# B008_-_Xino_RF_v1_5.net
KiCad netlist of a schematic drawn in EAGLE
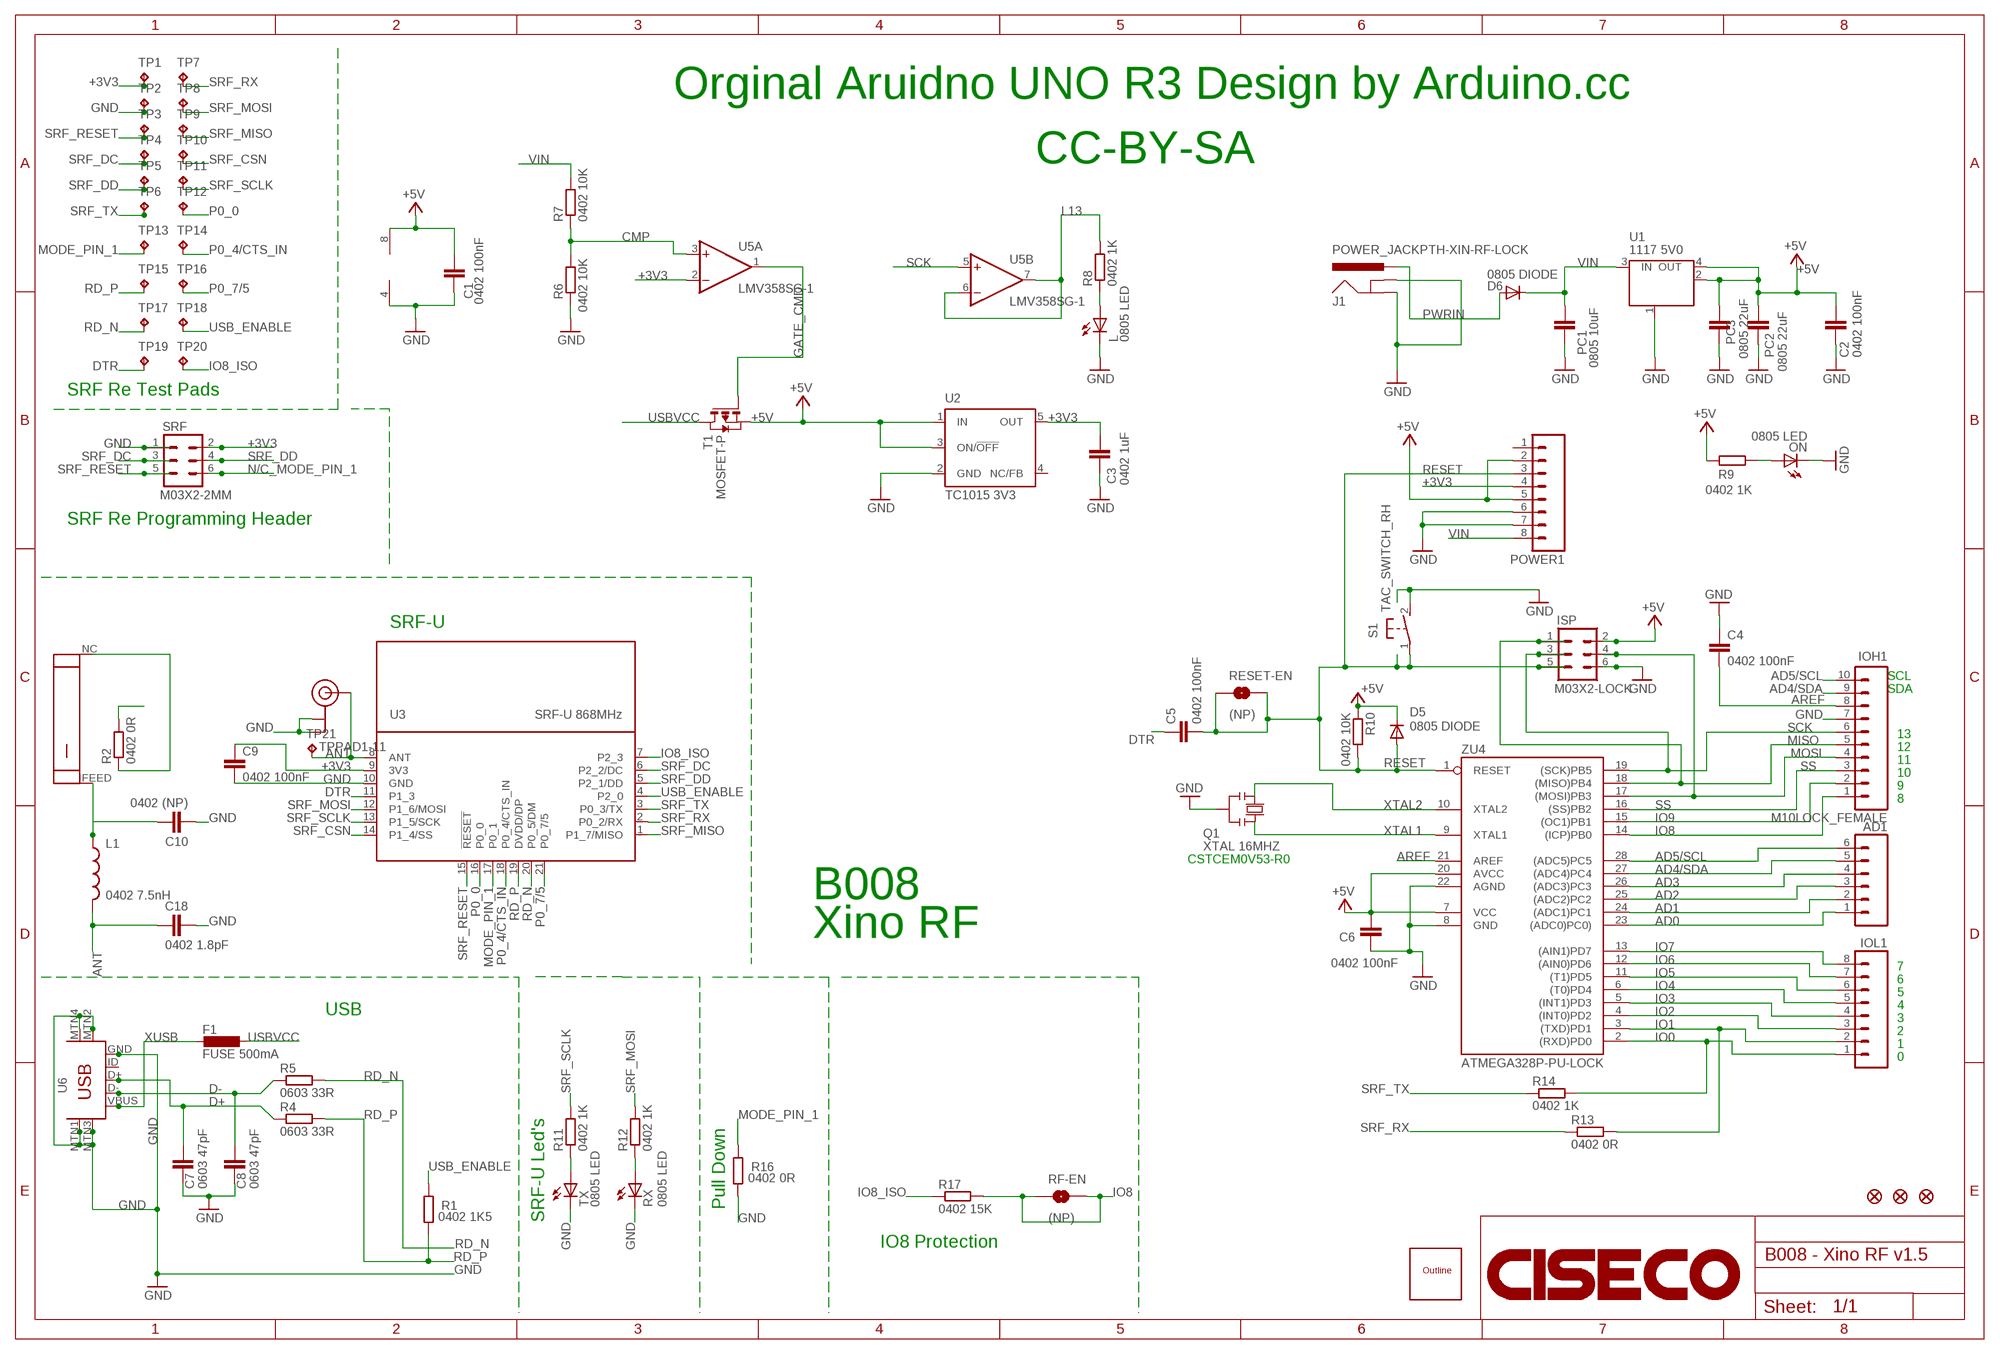
[diagram p0: schematic, sheet 1]

(export (version "E")
  (design (tool "Eeschema 10.0.6"))
  (components
    (comp (ref "AD1")
      (value "M06LOCK_FEMALE")
      (footprint "eagle-import:1X06_LOCK_FEMALE")
      (libsource (lib "eagle-import") (part "M06LOCK_FEMALE"))
    )
    (comp (ref "C1")
      (value "0402 100nF")
      (footprint "eagle-import:C0402-SMALLER")
      (libsource (lib "eagle-import") (part "C-EUC0402-SMALLER"))
    )
    (comp (ref "C2")
      (value "0402 100nF")
      (footprint "eagle-import:C0402-SMALLER")
      (libsource (lib "eagle-import") (part "C-EUC0402-SMALLER"))
    )
    (comp (ref "C3")
      (value "0402 1uF")
      (footprint "eagle-import:C0402-SMALLER")
      (libsource (lib "eagle-import") (part "C-EUC0402-SMALLER"))
    )
    (comp (ref "C4")
      (value "0402 100nF")
      (footprint "eagle-import:C0402-SMALLER")
      (libsource (lib "eagle-import") (part "C-EUC0402-SMALLER"))
    )
    (comp (ref "C5")
      (value "0402 100nF")
      (footprint "eagle-import:C0402-SMALLER")
      (libsource (lib "eagle-import") (part "C-EUC0402-SMALLER"))
    )
    (comp (ref "C6")
      (value "0402 100nF")
      (footprint "eagle-import:C0603-ROUND")
      (libsource (lib "eagle-import") (part "C-EU0603-RND"))
    )
    (comp (ref "C7")
      (value "0603 47pF")
      (footprint "eagle-import:C0603K-SMALL")
      (libsource (lib "eagle-import") (part "C-EUC0603K-SMALL"))
    )
    (comp (ref "C8")
      (value "0603 47pF")
      (footprint "eagle-import:C0603K-SMALL")
      (libsource (lib "eagle-import") (part "C-EUC0603K-SMALL"))
    )
    (comp (ref "C9")
      (value "0402 100nF")
      (footprint "eagle-import:C0402-SMALLER")
      (libsource (lib "eagle-import") (part "C-EUC0402-SMALLER"))
    )
    (comp (ref "C10")
      (value "0402 (NP)")
      (footprint "eagle-import:C0402-SMALLER")
      (libsource (lib "eagle-import") (part "C-EUC0402-SMALLER"))
    )
    (comp (ref "C18")
      (value "0402 1.8pF")
      (footprint "eagle-import:C0402-SMALLER")
      (libsource (lib "eagle-import") (part "C-EUC0402-SMALLER"))
    )
    (comp (ref "D5")
      (value "0805 DIODE")
      (footprint "eagle-import:0805-DIODE")
      (libsource (lib "eagle-import") (part "DIODE-0805"))
    )
    (comp (ref "D6")
      (value "0805 DIODE")
      (footprint "eagle-import:0805-DIODE")
      (libsource (lib "eagle-import") (part "DIODE-0805"))
    )
    (comp (ref "F1")
      (value "FUSE 500mA")
      (footprint "eagle-import:L1812")
      (libsource (lib "eagle-import") (part "L-EUL1812"))
    )
    (comp (ref "FD1")
      (value "FIDUCIAL1X2.5-STOP")
      (footprint "eagle-import:FIDUCIAL-1X2.5-STOP")
      (libsource (lib "eagle-import") (part "FIDUCIAL1X2.5-STOP"))
    )
    (comp (ref "FD2")
      (value "FIDUCIAL1X2.5-STOP")
      (footprint "eagle-import:FIDUCIAL-1X2.5-STOP")
      (libsource (lib "eagle-import") (part "FIDUCIAL1X2.5-STOP"))
    )
    (comp (ref "FD3")
      (value "FIDUCIAL1X2.5-STOP")
      (footprint "eagle-import:FIDUCIAL-1X2.5-STOP")
      (libsource (lib "eagle-import") (part "FIDUCIAL1X2.5-STOP"))
    )
    (comp (ref "IOH1")
      (value "M10LOCK_FEMALE")
      (footprint "eagle-import:1X10_LOCK_FEMALE")
      (libsource (lib "eagle-import") (part "M10LOCK_FEMALE"))
    )
    (comp (ref "IOL1")
      (value "M08LOCK_FEMALE")
      (footprint "eagle-import:1X08_LOCK_FEMALE")
      (libsource (lib "eagle-import") (part "M08LOCK_FEMALE"))
    )
    (comp (ref "ISP")
      (value "M03X2-LOCK")
      (footprint "eagle-import:2X3_LOCK")
      (libsource (lib "eagle-import") (part "M03X2-LOCK"))
    )
    (comp (ref "J1")
      (value "POWER_JACKPTH-XIN-RF-LOCK")
      (footprint "eagle-import:POWER_JACK_PTH_XINO_RF_LOCK")
      (libsource (lib "eagle-import") (part "POWER_JACKPTH-XIN-RF-LOCK"))
    )
    (comp (ref "L")
      (value "0805 LED")
      (footprint "eagle-import:LED-0805-1206")
      (libsource (lib "eagle-import") (part "LED0805-1206"))
    )
    (comp (ref "L1")
      (value "0402 7.5nH")
      (footprint "eagle-import:C0402-SMALLER")
      (libsource (lib "eagle-import") (part "INDUCTOR0402-SMALLER"))
    )
    (comp (ref "ON")
      (value "0805 LED")
      (footprint "eagle-import:LED-0805-1206")
      (libsource (lib "eagle-import") (part "LED0805-1206"))
    )
    (comp (ref "PC1")
      (value "0805 10uF")
      (footprint "eagle-import:C0805K")
      (libsource (lib "eagle-import") (part "C-EUC0805K"))
    )
    (comp (ref "PC2")
      (value "0805 22uF")
      (footprint "eagle-import:C0805K")
      (libsource (lib "eagle-import") (part "C-EUC0805K"))
    )
    (comp (ref "PC3")
      (value "0805 22uF")
      (footprint "eagle-import:C0805K")
      (libsource (lib "eagle-import") (part "C-EUC0805K"))
    )
    (comp (ref "POWER1")
      (value "M08LOCK_FEMALE")
      (footprint "eagle-import:1X08_LOCK_FEMALE")
      (libsource (lib "eagle-import") (part "M08LOCK_FEMALE"))
    )
    (comp (ref "Q1")
      (value "XTAL 16MHZ")
      (footprint "eagle-import:RESONATOR")
      (libsource (lib "eagle-import") (part "RESONATORMU"))
    )
    (comp (ref "R1")
      (value "0402 1K5")
      (footprint "eagle-import:R0402-SMALLER")
      (libsource (lib "eagle-import") (part "R-EU_R0402-SMALLER"))
    )
    (comp (ref "R2")
      (value "0402 0R")
      (footprint "eagle-import:R0402-SMALLER")
      (libsource (lib "eagle-import") (part "R-EU_R0402-SMALLER"))
    )
    (comp (ref "R4")
      (value "0603 33R")
      (footprint "eagle-import:C0603K-SMALL")
      (libsource (lib "eagle-import") (part "R-EU_0603K-SMALL"))
    )
    (comp (ref "R5")
      (value "0603 33R")
      (footprint "eagle-import:C0603K-SMALL")
      (libsource (lib "eagle-import") (part "R-EU_0603K-SMALL"))
    )
    (comp (ref "R6")
      (value "0402 10K")
      (footprint "eagle-import:R0402-SMALLER")
      (libsource (lib "eagle-import") (part "R-EU_R0402-SMALLER"))
    )
    (comp (ref "R7")
      (value "0402 10K")
      (footprint "eagle-import:R0402-SMALLER")
      (libsource (lib "eagle-import") (part "R-EU_R0402-SMALLER"))
    )
    (comp (ref "R8")
      (value "0402 1K")
      (footprint "eagle-import:R0402-SMALLER")
      (libsource (lib "eagle-import") (part "R-EU_R0402-SMALLER"))
    )
    (comp (ref "R9")
      (value "0402 1K")
      (footprint "eagle-import:R0402-SMALLER")
      (libsource (lib "eagle-import") (part "R-EU_R0402-SMALLER"))
    )
    (comp (ref "R10")
      (value "0402 10K")
      (footprint "eagle-import:R0402-SMALLER")
      (libsource (lib "eagle-import") (part "R-EU_R0402-SMALLER"))
    )
    (comp (ref "R11")
      (value "0402 1K")
      (footprint "eagle-import:R0402-SMALLER")
      (libsource (lib "eagle-import") (part "R-EU_R0402-SMALLER"))
    )
    (comp (ref "R12")
      (value "0402 1K")
      (footprint "eagle-import:R0402-SMALLER")
      (libsource (lib "eagle-import") (part "R-EU_R0402-SMALLER"))
    )
    (comp (ref "R13")
      (value "0402 0R")
      (footprint "eagle-import:R0402-SMALLER")
      (libsource (lib "eagle-import") (part "R-EU_R0402-SMALLER"))
    )
    (comp (ref "R14")
      (value "0402 1K")
      (footprint "eagle-import:R0402-SMALLER")
      (libsource (lib "eagle-import") (part "R-EU_R0402-SMALLER"))
    )
    (comp (ref "R16")
      (value "0402 0R")
      (footprint "eagle-import:R0402-SMALLER")
      (libsource (lib "eagle-import") (part "R-EU_R0402-SMALLER"))
    )
    (comp (ref "R17")
      (value "0402 15K")
      (footprint "eagle-import:R0402-SMALLER")
      (libsource (lib "eagle-import") (part "R-EU_R0402-SMALLER"))
    )
    (comp (ref "RESET-EN")
      (value "(NP)")
      (footprint "eagle-import:SJ")
      (libsource (lib "eagle-import") (part "SOLDERJUMPERNO-SJ"))
    )
    (comp (ref "RF-EN")
      (value "(NP)")
      (footprint "eagle-import:SJ")
      (libsource (lib "eagle-import") (part "SOLDERJUMPERNO-SJ"))
    )
    (comp (ref "RX")
      (value "0805 LED")
      (footprint "eagle-import:LED-0805-1206")
      (libsource (lib "eagle-import") (part "LED0805-1206"))
    )
    (comp (ref "S1")
      (value "TAC_SWITCH_RH")
      (footprint "eagle-import:B3F-31XX")
      (libsource (lib "eagle-import") (part "TAC_SWITCH_RH"))
    )
    (comp (ref "SRF")
      (value "M03X2-2MM")
      (footprint "eagle-import:2X3_2MM")
      (libsource (lib "eagle-import") (part "M03X2-2MM"))
    )
    (comp (ref "T1")
      (value "MOSFET-P")
      (footprint "eagle-import:SOT-23")
      (libsource (lib "eagle-import") (part "PMOSSOT23"))
    )
    (comp (ref "TP1")
      (value "TPB1,27")
      (footprint "eagle-import:B1,27")
      (libsource (lib "eagle-import") (part "testpad_TPB1,27"))
    )
    (comp (ref "TP2")
      (value "TPB1,27")
      (footprint "eagle-import:B1,27")
      (libsource (lib "eagle-import") (part "testpad_TPB1,27"))
    )
    (comp (ref "TP3")
      (value "TPB1,27")
      (footprint "eagle-import:B1,27")
      (libsource (lib "eagle-import") (part "testpad_TPB1,27"))
    )
    (comp (ref "TP4")
      (value "TPB1,27")
      (footprint "eagle-import:B1,27")
      (libsource (lib "eagle-import") (part "testpad_TPB1,27"))
    )
    (comp (ref "TP5")
      (value "TPB1,27")
      (footprint "eagle-import:B1,27")
      (libsource (lib "eagle-import") (part "testpad_TPB1,27"))
    )
    (comp (ref "TP6")
      (value "TPB1,27")
      (footprint "eagle-import:B1,27")
      (libsource (lib "eagle-import") (part "testpad_TPB1,27"))
    )
    (comp (ref "TP7")
      (value "TPB1,27")
      (footprint "eagle-import:B1,27")
      (libsource (lib "eagle-import") (part "testpad_TPB1,27"))
    )
    (comp (ref "TP8")
      (value "TPB1,27")
      (footprint "eagle-import:B1,27")
      (libsource (lib "eagle-import") (part "testpad_TPB1,27"))
    )
    (comp (ref "TP9")
      (value "TPB1,27")
      (footprint "eagle-import:B1,27")
      (libsource (lib "eagle-import") (part "testpad_TPB1,27"))
    )
    (comp (ref "TP10")
      (value "TPB1,27")
      (footprint "eagle-import:B1,27")
      (libsource (lib "eagle-import") (part "testpad_TPB1,27"))
    )
    (comp (ref "TP11")
      (value "TPB1,27")
      (footprint "eagle-import:B1,27")
      (libsource (lib "eagle-import") (part "testpad_TPB1,27"))
    )
    (comp (ref "TP12")
      (value "TPB1,27")
      (footprint "eagle-import:B1,27")
      (libsource (lib "eagle-import") (part "testpad_TPB1,27"))
    )
    (comp (ref "TP13")
      (value "TPB1,27")
      (footprint "eagle-import:B1,27")
      (libsource (lib "eagle-import") (part "testpad_TPB1,27"))
    )
    (comp (ref "TP14")
      (value "TPB1,27")
      (footprint "eagle-import:B1,27")
      (libsource (lib "eagle-import") (part "testpad_TPB1,27"))
    )
    (comp (ref "TP15")
      (value "TPB1,27")
      (footprint "eagle-import:B1,27")
      (libsource (lib "eagle-import") (part "testpad_TPB1,27"))
    )
    (comp (ref "TP16")
      (value "TPB1,27")
      (footprint "eagle-import:B1,27")
      (libsource (lib "eagle-import") (part "testpad_TPB1,27"))
    )
    (comp (ref "TP17")
      (value "TPB1,27")
      (footprint "eagle-import:B1,27")
      (libsource (lib "eagle-import") (part "testpad_TPB1,27"))
    )
    (comp (ref "TP18")
      (value "TPB1,27")
      (footprint "eagle-import:B1,27")
      (libsource (lib "eagle-import") (part "testpad_TPB1,27"))
    )
    (comp (ref "TP19")
      (value "TPB1,27")
      (footprint "eagle-import:B1,27")
      (libsource (lib "eagle-import") (part "testpad_TPB1,27"))
    )
    (comp (ref "TP20")
      (value "TPB1,27")
      (footprint "eagle-import:B1,27")
      (libsource (lib "eagle-import") (part "testpad_TPB1,27"))
    )
    (comp (ref "TP21")
      (value "TPPAD1-11")
      (footprint "eagle-import:P1-11")
      (libsource (lib "eagle-import") (part "TPPAD1-11"))
    )
    (comp (ref "TX")
      (value "0805 LED")
      (footprint "eagle-import:LED-0805-1206")
      (libsource (lib "eagle-import") (part "LED0805-1206"))
    )
    (comp (ref "U$1")
      (value "CISECO-MEDIUM")
      (footprint "eagle-import:CISECO-1.3MM")
      (libsource (lib "eagle-import") (part "CISECO-MEDIUM"))
    )
    (comp (ref "U$2")
      (value "ARDUINO-OUTLINE-MILL-VSCORE")
      (footprint "eagle-import:ARDUINO-OUTLINE-MILL-VSCORE")
      (libsource (lib "eagle-import") (part "ARDUINO-OUTLINE-MILL-VSCORE"))
    )
    (comp (ref "U$3")
      (value "CISECO-LARGE")
      (footprint "eagle-import:CISECO-4MM")
      (libsource (lib "eagle-import") (part "CISECO-LARGE"))
    )
    (comp (ref "U1")
      (value "1117 5V0")
      (footprint "eagle-import:SOT223")
      (libsource (lib "eagle-import") (part "MC33269ST-3.3T3"))
    )
    (comp (ref "U2")
      (value "TC1015 3V3")
      (footprint "eagle-import:SOT23-DBV")
      (libsource (lib "eagle-import") (part "LP2985-XXDBVR33"))
    )
    (comp (ref "U3")
      (value "SRF-U 868MHz")
      (footprint "eagle-import:SRF-LANDING-NO-ANT-1.2")
      (libsource (lib "eagle-import") (part "SRF-LANDING-NO-ANT-1.2"))
    )
    (comp (ref "U4")
      (value "JTICHIPANT")
      (footprint "eagle-import:JTICHIPANT-ROT")
      (libsource (lib "eagle-import") (part "JTICHIPANT-ROTATED"))
    )
    (comp (ref "U5")
      (value "LMV358SG-1")
      (footprint "eagle-import:SO08")
      (libsource (lib "eagle-import") (part "LMV358?MX"))
    )
    (comp (ref "U6")
      (value "USB-MINIB-5PIN")
      (footprint "eagle-import:USB-MINIB-CISECO-1")
      (libsource (lib "eagle-import") (part "USB-MINIB-5PIN-TWEAKED"))
    )
    (comp (ref "U11")
      (value "U.FL (NP)")
      (footprint "eagle-import:U.FL")
      (libsource (lib "eagle-import") (part "U.FL"))
    )
    (comp (ref "ZU4")
      (value "ATMEGA328P-PU-LOCK")
      (footprint "eagle-import:DIL28-3-LOCK")
      (libsource (lib "eagle-import") (part "ATMEGA328P-PU-LOCK"))
    )
  )
  (nets
    (net (code "1") (name "+5V") (class "Default")
      (node (ref "C1") (pin "2") (pinfunction "2_2") (pintype "passive"))
      (node (ref "C2") (pin "2") (pinfunction "2_2") (pintype "passive"))
      (node (ref "C6") (pin "2") (pinfunction "2_2") (pintype "passive"))
      (node (ref "D5") (pin "C") (pinfunction "C_C") (pintype "passive"))
      (node (ref "ISP") (pin "2") (pinfunction "2_2") (pintype "passive"))
      (node (ref "PC2") (pin "1") (pinfunction "1_1") (pintype "passive"))
      (node (ref "PC3") (pin "1") (pinfunction "1_1") (pintype "passive"))
      (node (ref "POWER1") (pin "2") (pinfunction "2_2") (pintype "passive"))
      (node (ref "POWER1") (pin "5") (pinfunction "5_5") (pintype "passive"))
      (node (ref "R10") (pin "1") (pinfunction "1_1") (pintype "passive"))
      (node (ref "R9") (pin "2") (pinfunction "2_2") (pintype "passive"))
      (node (ref "T1") (pin "2") (pinfunction "S_2") (pintype "passive"))
      (node (ref "U1") (pin "2") (pinfunction "OUT_2") (pintype "passive"))
      (node (ref "U1") (pin "4") (pinfunction "OUT_4") (pintype "passive"))
      (node (ref "U2") (pin "1") (pinfunction "IN_1") (pintype "input"))
      (node (ref "U2") (pin "3") (pinfunction "ON/~{OFF}_3") (pintype "input"))
      (node (ref "U5") (pin "8") (pinfunction "V+_8") (pintype "power_in"))
      (node (ref "ZU4") (pin "20") (pinfunction "AVCC_20") (pintype "power_in"))
      (node (ref "ZU4") (pin "7") (pinfunction "VCC_7") (pintype "power_in"))
    )
    (net (code "2") (name "/+3V3") (class "Default")
      (node (ref "C3") (pin "2") (pinfunction "2_2") (pintype "passive"))
      (node (ref "C9") (pin "1") (pinfunction "1_1") (pintype "passive"))
      (node (ref "POWER1") (pin "4") (pinfunction "4_4") (pintype "passive"))
      (node (ref "SRF") (pin "2") (pinfunction "2_2") (pintype "passive"))
      (node (ref "TP1") (pin "TP") (pinfunction "TP_TP") (pintype "input"))
      (node (ref "U2") (pin "5") (pinfunction "OUT_5") (pintype "passive"))
      (node (ref "U3") (pin "9") (pinfunction "3V3_9") (pintype "power_in"))
      (node (ref "U5") (pin "2") (pinfunction "-IN_2") (pintype "input"))
    )
    (net (code "3") (name "/AD0") (class "Default")
      (node (ref "AD1") (pin "1") (pinfunction "1_1") (pintype "passive"))
      (node (ref "ZU4") (pin "23") (pinfunction "(ADC0)PC0)_23") (pintype "bidirectional"))
    )
    (net (code "4") (name "/AD1") (class "Default")
      (node (ref "AD1") (pin "2") (pinfunction "2_2") (pintype "passive"))
      (node (ref "ZU4") (pin "24") (pinfunction "(ADC1)PC1_24") (pintype "bidirectional"))
    )
    (net (code "5") (name "/AD2") (class "Default")
      (node (ref "AD1") (pin "3") (pinfunction "3_3") (pintype "passive"))
      (node (ref "ZU4") (pin "25") (pinfunction "(ADC2)PC2_25") (pintype "bidirectional"))
    )
    (net (code "6") (name "/AD3") (class "Default")
      (node (ref "AD1") (pin "4") (pinfunction "4_4") (pintype "passive"))
      (node (ref "ZU4") (pin "26") (pinfunction "(ADC3)PC3_26") (pintype "bidirectional"))
    )
    (net (code "7") (name "/AD4{slash}SDA") (class "Default")
      (node (ref "AD1") (pin "5") (pinfunction "5_5") (pintype "passive"))
      (node (ref "IOH1") (pin "9") (pinfunction "9_9") (pintype "passive"))
      (node (ref "ZU4") (pin "27") (pinfunction "(ADC4)PC4_27") (pintype "bidirectional"))
    )
    (net (code "8") (name "/AD5{slash}SCL") (class "Default")
      (node (ref "AD1") (pin "6") (pinfunction "6_6") (pintype "passive"))
      (node (ref "IOH1") (pin "10") (pinfunction "10_10") (pintype "passive"))
      (node (ref "ZU4") (pin "28") (pinfunction "(ADC5)PC5_28") (pintype "bidirectional"))
    )
    (net (code "9") (name "/ANT") (class "Default")
      (node (ref "C18") (pin "1") (pinfunction "1_1") (pintype "passive"))
      (node (ref "L1") (pin "2") (pinfunction "2_2") (pintype "passive"))
      (node (ref "TP21") (pin "TP") (pinfunction "TP_TP") (pintype "input"))
      (node (ref "U11") (pin "P$3") (pinfunction "SIGNAL_P$3") (pintype "bidirectional"))
      (node (ref "U3") (pin "8") (pinfunction "ANT_8") (pintype "output"))
    )
    (net (code "10") (name "/AREF") (class "Default")
      (node (ref "C4") (pin "2") (pinfunction "2_2") (pintype "passive"))
      (node (ref "IOH1") (pin "8") (pinfunction "8_8") (pintype "passive"))
      (node (ref "ZU4") (pin "21") (pinfunction "AREF_21") (pintype "passive"))
    )
    (net (code "11") (name "/CMP") (class "Default")
      (node (ref "R6") (pin "2") (pinfunction "2_2") (pintype "passive"))
      (node (ref "R7") (pin "1") (pinfunction "1_1") (pintype "passive"))
      (node (ref "U5") (pin "3") (pinfunction "+IN_3") (pintype "input"))
    )
    (net (code "12") (name "/D+") (class "Default")
      (node (ref "C7") (pin "1") (pinfunction "1_1") (pintype "passive"))
      (node (ref "R4") (pin "1") (pinfunction "1_1") (pintype "passive"))
      (node (ref "U6") (pin "D+") (pinfunction "D+_D+") (pintype "bidirectional"))
    )
    (net (code "13") (name "/D-") (class "Default")
      (node (ref "C8") (pin "1") (pinfunction "1_1") (pintype "passive"))
      (node (ref "R5") (pin "1") (pinfunction "1_1") (pintype "passive"))
      (node (ref "U6") (pin "D-") (pinfunction "D-_D-") (pintype "bidirectional"))
    )
    (net (code "14") (name "/DTR") (class "Default")
      (node (ref "C5") (pin "1") (pinfunction "1_1") (pintype "passive"))
      (node (ref "TP19") (pin "TP") (pinfunction "TP_TP") (pintype "input"))
      (node (ref "U3") (pin "11") (pinfunction "P1_3_11") (pintype "bidirectional"))
    )
    (net (code "15") (name "/GATE_CMD") (class "Default")
      (node (ref "T1") (pin "3") (pinfunction "G_3") (pintype "passive"))
      (node (ref "U5") (pin "1") (pinfunction "OUT_1") (pintype "output"))
    )
    (net (code "16") (name "/IO0") (class "Default")
      (node (ref "IOL1") (pin "1") (pinfunction "1_1") (pintype "passive"))
      (node (ref "R14") (pin "2") (pinfunction "2_2") (pintype "passive"))
      (node (ref "ZU4") (pin "2") (pinfunction "(RXD)PD0_2") (pintype "bidirectional"))
    )
    (net (code "17") (name "/IO1") (class "Default")
      (node (ref "IOL1") (pin "2") (pinfunction "2_2") (pintype "passive"))
      (node (ref "R13") (pin "2") (pinfunction "2_2") (pintype "passive"))
      (node (ref "ZU4") (pin "3") (pinfunction "(TXD)PD1_3") (pintype "bidirectional"))
    )
    (net (code "18") (name "/IO2") (class "Default")
      (node (ref "IOL1") (pin "3") (pinfunction "3_3") (pintype "passive"))
      (node (ref "ZU4") (pin "4") (pinfunction "(INT0)PD2_4") (pintype "bidirectional"))
    )
    (net (code "19") (name "/IO3") (class "Default")
      (node (ref "IOL1") (pin "4") (pinfunction "4_4") (pintype "passive"))
      (node (ref "ZU4") (pin "5") (pinfunction "(INT1)PD3_5") (pintype "bidirectional"))
    )
    (net (code "20") (name "/IO4") (class "Default")
      (node (ref "IOL1") (pin "5") (pinfunction "5_5") (pintype "passive"))
      (node (ref "ZU4") (pin "6") (pinfunction "(T0)PD4_6") (pintype "bidirectional"))
    )
    (net (code "21") (name "/IO5") (class "Default")
      (node (ref "IOL1") (pin "6") (pinfunction "6_6") (pintype "passive"))
      (node (ref "ZU4") (pin "11") (pinfunction "(T1)PD5_11") (pintype "bidirectional"))
    )
    (net (code "22") (name "/IO6") (class "Default")
      (node (ref "IOL1") (pin "7") (pinfunction "7_7") (pintype "passive"))
      (node (ref "ZU4") (pin "12") (pinfunction "(AIN0)PD6_12") (pintype "bidirectional"))
    )
    (net (code "23") (name "/IO7") (class "Default")
      (node (ref "IOL1") (pin "8") (pinfunction "8_8") (pintype "passive"))
      (node (ref "ZU4") (pin "13") (pinfunction "(AIN1)PD7_13") (pintype "bidirectional"))
    )
    (net (code "24") (name "/IO8") (class "Default")
      (node (ref "IOH1") (pin "1") (pinfunction "1_1") (pintype "passive"))
      (node (ref "R17") (pin "2") (pinfunction "2_2") (pintype "passive"))
      (node (ref "RF-EN") (pin "1") (pinfunction "1_1") (pintype "passive"))
      (node (ref "RF-EN") (pin "2") (pinfunction "2_2") (pintype "passive"))
      (node (ref "ZU4") (pin "14") (pinfunction "(ICP)PB0_14") (pintype "bidirectional"))
    )
    (net (code "25") (name "/IO8_ISO") (class "Default")
      (node (ref "R17") (pin "1") (pinfunction "1_1") (pintype "passive"))
      (node (ref "TP20") (pin "TP") (pinfunction "TP_TP") (pintype "input"))
      (node (ref "U3") (pin "7") (pinfunction "P2_3_7") (pintype "bidirectional"))
    )
    (net (code "26") (name "/IO9") (class "Default")
      (node (ref "IOH1") (pin "2") (pinfunction "2_2") (pintype "passive"))
      (node (ref "ZU4") (pin "15") (pinfunction "(OC1)PB1_15") (pintype "bidirectional"))
    )
    (net (code "27") (name "/L13") (class "Default")
      (node (ref "R8") (pin "2") (pinfunction "2_2") (pintype "passive"))
      (node (ref "U5") (pin "6") (pinfunction "-IN_6") (pintype "input"))
      (node (ref "U5") (pin "7") (pinfunction "OUT_7") (pintype "output"))
    )
    (net (code "28") (name "/MISO") (class "Default")
      (node (ref "IOH1") (pin "5") (pinfunction "5_5") (pintype "passive"))
      (node (ref "ISP") (pin "1") (pinfunction "1_1") (pintype "passive"))
      (node (ref "ZU4") (pin "18") (pinfunction "(MISO)PB4_18") (pintype "bidirectional"))
    )
    (net (code "29") (name "/MODE_PIN_1") (class "Default")
      (node (ref "R16") (pin "2") (pinfunction "2_2") (pintype "passive"))
      (node (ref "TP13") (pin "TP") (pinfunction "TP_TP") (pintype "input"))
      (node (ref "U3") (pin "17") (pinfunction "P0_1_17") (pintype "bidirectional"))
    )
    (net (code "30") (name "/MOSI") (class "Default")
      (node (ref "IOH1") (pin "4") (pinfunction "4_4") (pintype "passive"))
      (node (ref "ISP") (pin "4") (pinfunction "4_4") (pintype "passive"))
      (node (ref "ZU4") (pin "17") (pinfunction "(MOSI)PB3_17") (pintype "bidirectional"))
    )
    (net (code "31") (name "/N{slash}C_MODE_PIN_1") (class "Default")
      (node (ref "SRF") (pin "6") (pinfunction "6_6") (pintype "passive"))
    )
    (net (code "32") (name "/P0_0") (class "Default")
      (node (ref "TP12") (pin "TP") (pinfunction "TP_TP") (pintype "input"))
      (node (ref "U3") (pin "16") (pinfunction "P0_0_16") (pintype "bidirectional"))
    )
    (net (code "33") (name "/P0_4{slash}CTS_IN") (class "Default")
      (node (ref "TP14") (pin "TP") (pinfunction "TP_TP") (pintype "input"))
      (node (ref "U3") (pin "18") (pinfunction "P0_4/CTS_IN_18") (pintype "bidirectional"))
    )
    (net (code "34") (name "/P0_7{slash}5") (class "Default")
      (node (ref "TP16") (pin "TP") (pinfunction "TP_TP") (pintype "input"))
      (node (ref "U3") (pin "21") (pinfunction "P0_7/5_21") (pintype "bidirectional"))
    )
    (net (code "35") (name "/PWRIN") (class "Default")
      (node (ref "D6") (pin "A") (pinfunction "A_A") (pintype "passive"))
      (node (ref "J1") (pin "PWR") (pinfunction "PWR_PWR") (pintype "bidirectional"))
    )
    (net (code "36") (name "/RD_N") (class "Default")
      (node (ref "R5") (pin "2") (pinfunction "2_2") (pintype "passive"))
      (node (ref "TP17") (pin "TP") (pinfunction "TP_TP") (pintype "input"))
      (node (ref "U3") (pin "20") (pinfunction "P0_5/DM_20") (pintype "bidirectional"))
    )
    (net (code "37") (name "/RD_P") (class "Default")
      (node (ref "R1") (pin "1") (pinfunction "1_1") (pintype "passive"))
      (node (ref "R4") (pin "2") (pinfunction "2_2") (pintype "passive"))
      (node (ref "TP15") (pin "TP") (pinfunction "TP_TP") (pintype "input"))
      (node (ref "U3") (pin "19") (pinfunction "DVDD/DP_19") (pintype "bidirectional"))
    )
    (net (code "38") (name "/RESET") (class "Default")
      (node (ref "C5") (pin "2") (pinfunction "2_2") (pintype "passive"))
      (node (ref "D5") (pin "A") (pinfunction "A_A") (pintype "passive"))
      (node (ref "ISP") (pin "5") (pinfunction "5_5") (pintype "passive"))
      (node (ref "POWER1") (pin "3") (pinfunction "3_3") (pintype "passive"))
      (node (ref "R10") (pin "2") (pinfunction "2_2") (pintype "passive"))
      (node (ref "RESET-EN") (pin "1") (pinfunction "1_1") (pintype "passive"))
      (node (ref "RESET-EN") (pin "2") (pinfunction "2_2") (pintype "passive"))
      (node (ref "S1") (pin "1") (pinfunction "P_1") (pintype "passive"))
      (node (ref "ZU4") (pin "1") (pinfunction "RESET_1") (pintype "input"))
    )
    (net (code "39") (name "/SCK") (class "Default")
      (node (ref "IOH1") (pin "6") (pinfunction "6_6") (pintype "passive"))
      (node (ref "ISP") (pin "3") (pinfunction "3_3") (pintype "passive"))
      (node (ref "U5") (pin "5") (pinfunction "+IN_5") (pintype "input"))
      (node (ref "ZU4") (pin "19") (pinfunction "(SCK)PB5_19") (pintype "bidirectional"))
    )
    (net (code "40") (name "/SRF_CSN") (class "Default")
      (node (ref "TP10") (pin "TP") (pinfunction "TP_TP") (pintype "input"))
      (node (ref "U3") (pin "14") (pinfunction "P1_4/SS_14") (pintype "bidirectional"))
    )
    (net (code "41") (name "/SRF_DC") (class "Default")
      (node (ref "SRF") (pin "3") (pinfunction "3_3") (pintype "passive"))
      (node (ref "TP4") (pin "TP") (pinfunction "TP_TP") (pintype "input"))
      (node (ref "U3") (pin "6") (pinfunction "P2_2/DC_6") (pintype "bidirectional"))
    )
    (net (code "42") (name "/SRF_DD") (class "Default")
      (node (ref "SRF") (pin "4") (pinfunction "4_4") (pintype "passive"))
      (node (ref "TP5") (pin "TP") (pinfunction "TP_TP") (pintype "input"))
      (node (ref "U3") (pin "5") (pinfunction "P2_1/DD_5") (pintype "bidirectional"))
    )
    (net (code "43") (name "/SRF_MISO") (class "Default")
      (node (ref "TP9") (pin "TP") (pinfunction "TP_TP") (pintype "input"))
      (node (ref "U3") (pin "1") (pinfunction "P1_7/MISO_1") (pintype "bidirectional"))
    )
    (net (code "44") (name "/SRF_MOSI") (class "Default")
      (node (ref "R12") (pin "2") (pinfunction "2_2") (pintype "passive"))
      (node (ref "TP8") (pin "TP") (pinfunction "TP_TP") (pintype "input"))
      (node (ref "U3") (pin "12") (pinfunction "P1_6/MOSI_12") (pintype "bidirectional"))
    )
    (net (code "45") (name "/SRF_RESET") (class "Default")
      (node (ref "SRF") (pin "5") (pinfunction "5_5") (pintype "passive"))
      (node (ref "TP3") (pin "TP") (pinfunction "TP_TP") (pintype "input"))
      (node (ref "U3") (pin "15") (pinfunction "~{RESET}_15") (pintype "input"))
    )
    (net (code "46") (name "/SRF_RX") (class "Default")
      (node (ref "R13") (pin "1") (pinfunction "1_1") (pintype "passive"))
      (node (ref "TP7") (pin "TP") (pinfunction "TP_TP") (pintype "input"))
      (node (ref "U3") (pin "2") (pinfunction "P0_2/RX_2") (pintype "bidirectional"))
    )
    (net (code "47") (name "/SRF_SCLK") (class "Default")
      (node (ref "R11") (pin "2") (pinfunction "2_2") (pintype "passive"))
      (node (ref "TP11") (pin "TP") (pinfunction "TP_TP") (pintype "input"))
      (node (ref "U3") (pin "13") (pinfunction "P1_5/SCK_13") (pintype "bidirectional"))
    )
    (net (code "48") (name "/SRF_TX") (class "Default")
      (node (ref "R14") (pin "1") (pinfunction "1_1") (pintype "passive"))
      (node (ref "TP6") (pin "TP") (pinfunction "TP_TP") (pintype "input"))
      (node (ref "U3") (pin "3") (pinfunction "P0_3/TX_3") (pintype "bidirectional"))
    )
    (net (code "49") (name "/SS") (class "Default")
      (node (ref "IOH1") (pin "3") (pinfunction "3_3") (pintype "passive"))
      (node (ref "ZU4") (pin "16") (pinfunction "(SS)PB2_16") (pintype "bidirectional"))
    )
    (net (code "50") (name "/USBVCC") (class "Default")
      (node (ref "F1") (pin "1") (pinfunction "1_1") (pintype "passive"))
      (node (ref "T1") (pin "1") (pinfunction "D_1") (pintype "passive"))
    )
    (net (code "51") (name "/USB_ENABLE") (class "Default")
      (node (ref "R1") (pin "2") (pinfunction "2_2") (pintype "passive"))
      (node (ref "TP18") (pin "TP") (pinfunction "TP_TP") (pintype "input"))
      (node (ref "U3") (pin "4") (pinfunction "P2_0_4") (pintype "bidirectional"))
    )
    (net (code "52") (name "/VIN") (class "Default")
      (node (ref "D6") (pin "C") (pinfunction "C_C") (pintype "passive"))
      (node (ref "PC1") (pin "1") (pinfunction "1_1") (pintype "passive"))
      (node (ref "POWER1") (pin "8") (pinfunction "8_8") (pintype "passive"))
      (node (ref "R7") (pin "2") (pinfunction "2_2") (pintype "passive"))
      (node (ref "U1") (pin "3") (pinfunction "IN_3") (pintype "input"))
    )
    (net (code "53") (name "/XTAL1") (class "Default")
      (node (ref "Q1") (pin "3") (pinfunction "3_3") (pintype "passive"))
      (node (ref "ZU4") (pin "9") (pinfunction "XTAL1_9") (pintype "bidirectional"))
    )
    (net (code "54") (name "/XTAL2") (class "Default")
      (node (ref "Q1") (pin "1") (pinfunction "1_1") (pintype "passive"))
      (node (ref "ZU4") (pin "10") (pinfunction "XTAL2_10") (pintype "bidirectional"))
    )
    (net (code "55") (name "/XUSB") (class "Default")
      (node (ref "F1") (pin "2") (pinfunction "2_2") (pintype "passive"))
      (node (ref "U6") (pin "VBUS") (pinfunction "VBUS_VBUS") (pintype "bidirectional"))
    )
    (net (code "56") (name "GND") (class "Default")
      (node (ref "C1") (pin "1") (pinfunction "1_1") (pintype "passive"))
      (node (ref "C10") (pin "1") (pinfunction "1_1") (pintype "passive"))
      (node (ref "C18") (pin "2") (pinfunction "2_2") (pintype "passive"))
      (node (ref "C2") (pin "1") (pinfunction "1_1") (pintype "passive"))
      (node (ref "C3") (pin "1") (pinfunction "1_1") (pintype "passive"))
      (node (ref "C4") (pin "1") (pinfunction "1_1") (pintype "passive"))
      (node (ref "C6") (pin "1") (pinfunction "1_1") (pintype "passive"))
      (node (ref "C7") (pin "2") (pinfunction "2_2") (pintype "passive"))
      (node (ref "C8") (pin "2") (pinfunction "2_2") (pintype "passive"))
      (node (ref "C9") (pin "2") (pinfunction "2_2") (pintype "passive"))
      (node (ref "IOH1") (pin "7") (pinfunction "7_7") (pintype "passive"))
      (node (ref "ISP") (pin "6") (pinfunction "6_6") (pintype "passive"))
      (node (ref "J1") (pin "GND") (pinfunction "GND_GND") (pintype "bidirectional"))
      (node (ref "J1") (pin "GNDBREAK") (pinfunction "GNDBREAK_GNDBREAK") (pintype "bidirectional"))
      (node (ref "L") (pin "C") (pinfunction "C_C") (pintype "passive"))
      (node (ref "ON") (pin "C") (pinfunction "C_C") (pintype "passive"))
      (node (ref "PC1") (pin "2") (pinfunction "2_2") (pintype "passive"))
      (node (ref "PC2") (pin "2") (pinfunction "2_2") (pintype "passive"))
      (node (ref "PC3") (pin "2") (pinfunction "2_2") (pintype "passive"))
      (node (ref "POWER1") (pin "6") (pinfunction "6_6") (pintype "passive"))
      (node (ref "POWER1") (pin "7") (pinfunction "7_7") (pintype "passive"))
      (node (ref "Q1") (pin "2") (pinfunction "2_2") (pintype "passive"))
      (node (ref "R16") (pin "1") (pinfunction "1_1") (pintype "passive"))
      (node (ref "R6") (pin "1") (pinfunction "1_1") (pintype "passive"))
      (node (ref "RX") (pin "C") (pinfunction "C_C") (pintype "passive"))
      (node (ref "S1") (pin "2") (pinfunction "S_2") (pintype "passive"))
      (node (ref "SRF") (pin "1") (pinfunction "1_1") (pintype "passive"))
      (node (ref "TP2") (pin "TP") (pinfunction "TP_TP") (pintype "input"))
      (node (ref "TX") (pin "C") (pinfunction "C_C") (pintype "passive"))
      (node (ref "U1") (pin "1") (pinfunction "GND/ADJ_1") (pintype "input"))
      (node (ref "U11") (pin "P$1") (pinfunction "GND_P$1") (pintype "bidirectional"))
      (node (ref "U11") (pin "P$2") (pinfunction "GND_P$2") (pintype "bidirectional"))
      (node (ref "U2") (pin "2") (pinfunction "GND_2") (pintype "power_in"))
      (node (ref "U3") (pin "10") (pinfunction "GND_10") (pintype "power_in"))
      (node (ref "U5") (pin "4") (pinfunction "V-_4") (pintype "power_in"))
      (node (ref "U6") (pin "GND") (pinfunction "GND_GND") (pintype "bidirectional"))
      (node (ref "U6") (pin "MTN1") (pinfunction "MTN2_MTN1") (pintype "bidirectional"))
      (node (ref "U6") (pin "MTN2") (pinfunction "MTN3_MTN2") (pintype "bidirectional"))
      (node (ref "U6") (pin "MTN3") (pinfunction "MTN1_MTN3") (pintype "bidirectional"))
      (node (ref "U6") (pin "MTN4") (pinfunction "MTN4_MTN4") (pintype "bidirectional"))
      (node (ref "ZU4") (pin "22") (pinfunction "AGND_22") (pintype "power_in"))
      (node (ref "ZU4") (pin "8") (pinfunction "GND_8") (pintype "power_in"))
    )
    (net (code "57") (name "Net-(L-PadA)") (class "Default")
      (node (ref "L") (pin "A") (pinfunction "A_A") (pintype "passive"))
      (node (ref "R8") (pin "1") (pinfunction "1_1") (pintype "passive"))
    )
    (net (code "58") (name "Net-(ON-PadA)") (class "Default")
      (node (ref "ON") (pin "A") (pinfunction "A_A") (pintype "passive"))
      (node (ref "R9") (pin "1") (pinfunction "1_1") (pintype "passive"))
    )
    (net (code "59") (name "Net-(R11-Pad1)") (class "Default")
      (node (ref "R11") (pin "1") (pinfunction "1_1") (pintype "passive"))
      (node (ref "TX") (pin "A") (pinfunction "A_A") (pintype "passive"))
    )
    (net (code "60") (name "Net-(R12-Pad1)") (class "Default")
      (node (ref "R12") (pin "1") (pinfunction "1_1") (pintype "passive"))
      (node (ref "RX") (pin "A") (pinfunction "A_A") (pintype "passive"))
    )
    (net (code "61") (name "Net-(U4-P$1)") (class "Default")
      (node (ref "R2") (pin "1") (pinfunction "1_1") (pintype "passive"))
      (node (ref "U4") (pin "NC") (pinfunction "P$1_NC") (pintype "bidirectional"))
    )
    (net (code "62") (name "Net-(U4-P$2)") (class "Default")
      (node (ref "C10") (pin "2") (pinfunction "2_2") (pintype "passive"))
      (node (ref "L1") (pin "1") (pinfunction "1_1") (pintype "passive"))
      (node (ref "U4") (pin "FEED") (pinfunction "P$2_FEED") (pintype "bidirectional"))
    )
    (net (code "63") (name "unconnected-(POWER1-Pad1)") (class "Default")
      (node (ref "POWER1") (pin "1") (pinfunction "1_1") (pintype "passive"))
    )
    (net (code "64") (name "unconnected-(R2-Pad2)") (class "Default")
      (node (ref "R2") (pin "2") (pinfunction "2_2") (pintype "passive"))
    )
    (net (code "65") (name "unconnected-(U2-NC{slash}FB-Pad4)") (class "Default")
      (node (ref "U2") (pin "4") (pinfunction "NC/FB_4") (pintype "passive"))
    )
    (net (code "66") (name "unconnected-(U6-PadID)") (class "Default")
      (node (ref "U6") (pin "ID") (pinfunction "ID_ID") (pintype "bidirectional"))
    )
  )
)
